# PCB-ETH-TALLY.net
KiCad netlist of a schematic drawn in EAGLE
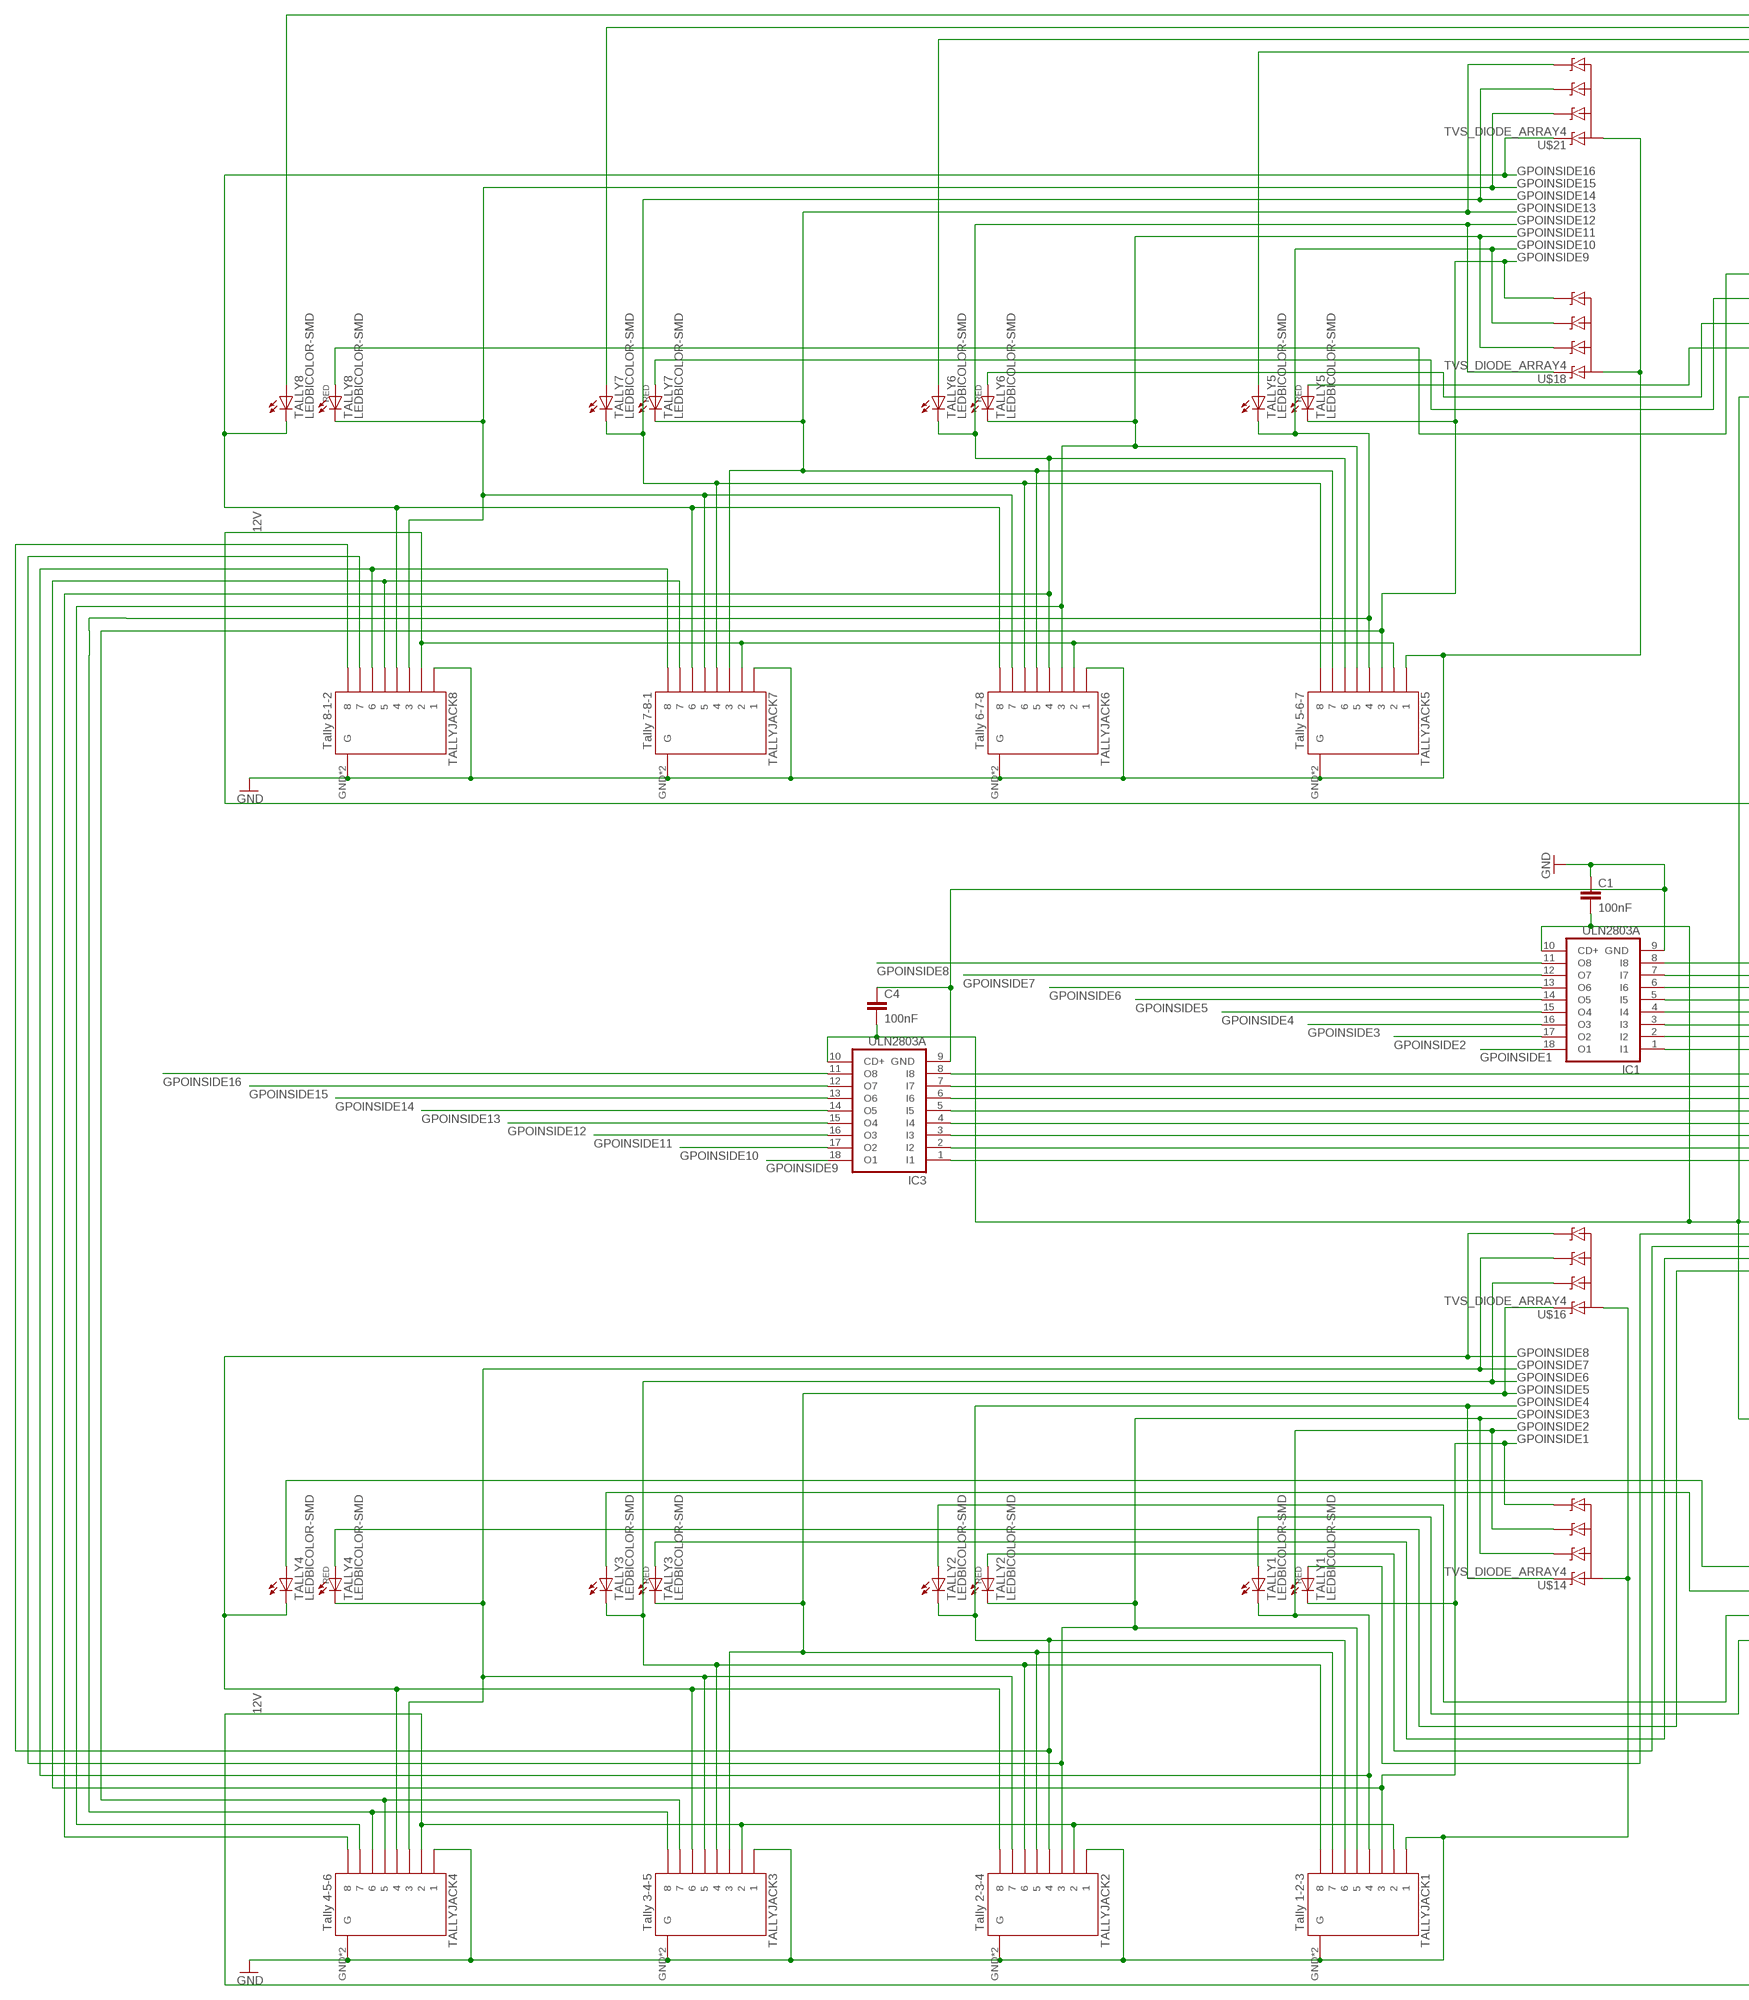
[diagram p0: schematic, sheet 1, part 1 of 2]
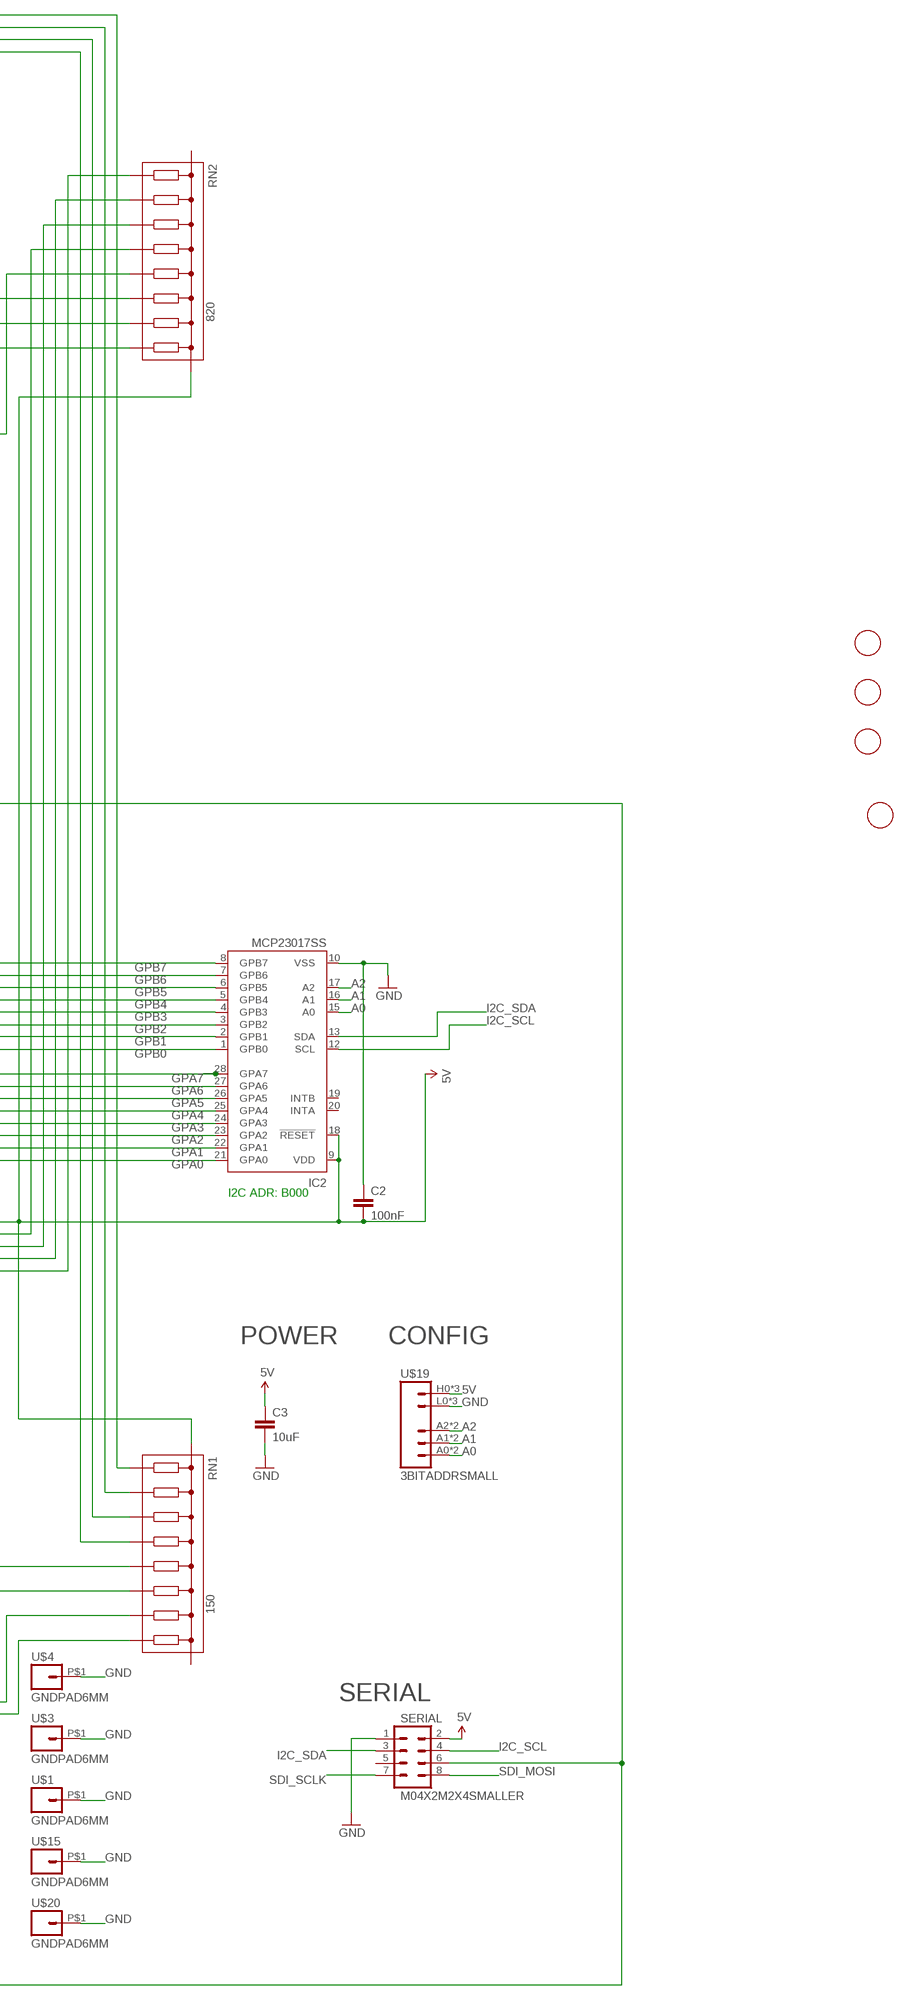
[diagram p1: schematic, sheet 1, part 2 of 2]

(export (version "E")
  (design (tool "Eeschema 10.0.6"))
  (components
    (comp (ref "C1")
      (value "100nF")
      (footprint "eagle-import:0805")
      (libsource (lib "eagle-import") (part "CAP0805"))
    )
    (comp (ref "C2")
      (value "100nF")
      (footprint "eagle-import:0603-CAP")
      (libsource (lib "eagle-import") (part "CAP0603-CAP"))
    )
    (comp (ref "C3")
      (value "10uF")
      (footprint "eagle-import:0805")
      (libsource (lib "eagle-import") (part "CAP0805"))
    )
    (comp (ref "C4")
      (value "100nF")
      (footprint "eagle-import:0805")
      (libsource (lib "eagle-import") (part "CAP0805"))
    )
    (comp (ref "IC1")
      (value "ULN2803A")
      (footprint "eagle-import:SO18W")
      (libsource (lib "eagle-import") (part "ULN2803ASO18W"))
    )
    (comp (ref "IC2")
      (value "MCP23017SS")
      (footprint "eagle-import:SSOP28")
      (fields (field (name "MF") "MICROCHIP") (field (name "MPN") "MCP23017-E/SS"))
      (libsource (lib "eagle-import") (part "MCP23017SS"))
    )
    (comp (ref "IC3")
      (value "ULN2803A")
      (footprint "eagle-import:SO18W")
      (libsource (lib "eagle-import") (part "ULN2803ASO18W"))
    )
    (comp (ref "RN1")
      (value "150")
      (footprint "eagle-import:EXBE")
      (libsource (lib "eagle-import") (part "EXBE"))
    )
    (comp (ref "RN2")
      (value "820")
      (footprint "eagle-import:EXBE")
      (libsource (lib "eagle-import") (part "EXBE"))
    )
    (comp (ref "SERIAL")
      (value "M04X2M2X4SMALLER")
      (footprint "eagle-import:M2X4SMALLER")
      (libsource (lib "eagle-import") (part "M04X2M2X4SMALLER"))
    )
    (comp (ref "TALLY1")
      (value "LEDBICOLOR-SMD")
      (footprint "eagle-import:LEDBICOLOR-SMD")
      (libsource (lib "eagle-import") (part "LEDBICOLOR-SMD"))
    )
    (comp (ref "TALLY2")
      (value "LEDBICOLOR-SMD")
      (footprint "eagle-import:LEDBICOLOR-SMD")
      (libsource (lib "eagle-import") (part "LEDBICOLOR-SMD"))
    )
    (comp (ref "TALLY3")
      (value "LEDBICOLOR-SMD")
      (footprint "eagle-import:LEDBICOLOR-SMD")
      (libsource (lib "eagle-import") (part "LEDBICOLOR-SMD"))
    )
    (comp (ref "TALLY4")
      (value "LEDBICOLOR-SMD")
      (footprint "eagle-import:LEDBICOLOR-SMD")
      (libsource (lib "eagle-import") (part "LEDBICOLOR-SMD"))
    )
    (comp (ref "TALLY5")
      (value "LEDBICOLOR-SMD")
      (footprint "eagle-import:LEDBICOLOR-SMD")
      (libsource (lib "eagle-import") (part "LEDBICOLOR-SMD"))
    )
    (comp (ref "TALLY6")
      (value "LEDBICOLOR-SMD")
      (footprint "eagle-import:LEDBICOLOR-SMD")
      (libsource (lib "eagle-import") (part "LEDBICOLOR-SMD"))
    )
    (comp (ref "TALLY7")
      (value "LEDBICOLOR-SMD")
      (footprint "eagle-import:LEDBICOLOR-SMD")
      (libsource (lib "eagle-import") (part "LEDBICOLOR-SMD"))
    )
    (comp (ref "TALLY8")
      (value "LEDBICOLOR-SMD")
      (footprint "eagle-import:LEDBICOLOR-SMD")
      (libsource (lib "eagle-import") (part "LEDBICOLOR-SMD"))
    )
    (comp (ref "TALLYJACK1")
      (value "Tally 1-2-3")
      (footprint "eagle-import:RJ45-8_GND_UPRIGHT")
      (libsource (lib "eagle-import") (part "RJ45-8_GNDUPRIGHT"))
    )
    (comp (ref "TALLYJACK2")
      (value "Tally 2-3-4")
      (footprint "eagle-import:RJ45-8_GND_UPRIGHT")
      (libsource (lib "eagle-import") (part "RJ45-8_GNDUPRIGHT"))
    )
    (comp (ref "TALLYJACK3")
      (value "Tally 3-4-5")
      (footprint "eagle-import:RJ45-8_GND_UPRIGHT")
      (libsource (lib "eagle-import") (part "RJ45-8_GNDUPRIGHT"))
    )
    (comp (ref "TALLYJACK4")
      (value "Tally 4-5-6")
      (footprint "eagle-import:RJ45-8_GND_UPRIGHT")
      (libsource (lib "eagle-import") (part "RJ45-8_GNDUPRIGHT"))
    )
    (comp (ref "TALLYJACK5")
      (value "Tally 5-6-7")
      (footprint "eagle-import:RJ45-8_GND_UPRIGHT")
      (libsource (lib "eagle-import") (part "RJ45-8_GNDUPRIGHT"))
    )
    (comp (ref "TALLYJACK6")
      (value "Tally 6-7-8")
      (footprint "eagle-import:RJ45-8_GND_UPRIGHT")
      (libsource (lib "eagle-import") (part "RJ45-8_GNDUPRIGHT"))
    )
    (comp (ref "TALLYJACK7")
      (value "Tally 7-8-1")
      (footprint "eagle-import:RJ45-8_GND_UPRIGHT")
      (libsource (lib "eagle-import") (part "RJ45-8_GNDUPRIGHT"))
    )
    (comp (ref "TALLYJACK8")
      (value "Tally 8-1-2")
      (footprint "eagle-import:RJ45-8_GND_UPRIGHT")
      (libsource (lib "eagle-import") (part "RJ45-8_GNDUPRIGHT"))
    )
    (comp (ref "U$1")
      (value "GNDPAD6MM")
      (footprint "eagle-import:3.2MMPAD6MM")
      (libsource (lib "eagle-import") (part "GNDPAD6MM"))
    )
    (comp (ref "U$3")
      (value "GNDPAD6MM")
      (footprint "eagle-import:3.2MMPAD6MM")
      (libsource (lib "eagle-import") (part "GNDPAD6MM"))
    )
    (comp (ref "U$4")
      (value "GNDPAD6MM")
      (footprint "eagle-import:3.2MMPAD6MM")
      (libsource (lib "eagle-import") (part "GNDPAD6MM"))
    )
    (comp (ref "U$5")
      (value "FIDUCIAL")
      (footprint "eagle-import:FIDUCIAL_1MM")
      (libsource (lib "eagle-import") (part "FIDUCIAL"))
    )
    (comp (ref "U$6")
      (value "FIDUCIAL")
      (footprint "eagle-import:FIDUCIAL_1MM")
      (libsource (lib "eagle-import") (part "FIDUCIAL"))
    )
    (comp (ref "U$8")
      (value "FIDUCIAL")
      (footprint "eagle-import:FIDUCIAL_1MM")
      (libsource (lib "eagle-import") (part "FIDUCIAL"))
    )
    (comp (ref "U$9")
      (value "FIDUCIAL")
      (footprint "eagle-import:FIDUCIAL_1MM")
      (libsource (lib "eagle-import") (part "FIDUCIAL"))
    )
    (comp (ref "U$14")
      (value "TVS_DIODE_ARRAY4")
      (footprint "eagle-import:SOT23-6L")
      (libsource (lib "eagle-import") (part "TVS_DIODE_ARRAY4"))
    )
    (comp (ref "U$15")
      (value "GNDPAD6MM")
      (footprint "eagle-import:3.2MMPAD6MM")
      (libsource (lib "eagle-import") (part "GNDPAD6MM"))
    )
    (comp (ref "U$16")
      (value "TVS_DIODE_ARRAY4")
      (footprint "eagle-import:SOT23-6L")
      (libsource (lib "eagle-import") (part "TVS_DIODE_ARRAY4"))
    )
    (comp (ref "U$18")
      (value "TVS_DIODE_ARRAY4")
      (footprint "eagle-import:SOT23-6L")
      (libsource (lib "eagle-import") (part "TVS_DIODE_ARRAY4"))
    )
    (comp (ref "U$19")
      (value "3BITADDRSMALL")
      (footprint "eagle-import:3BITADDR_SMALL")
      (libsource (lib "eagle-import") (part "3BITADDRSMALL"))
    )
    (comp (ref "U$20")
      (value "GNDPAD6MM")
      (footprint "eagle-import:3.2MMPAD6MM")
      (libsource (lib "eagle-import") (part "GNDPAD6MM"))
    )
    (comp (ref "U$21")
      (value "TVS_DIODE_ARRAY4")
      (footprint "eagle-import:SOT23-6L")
      (libsource (lib "eagle-import") (part "TVS_DIODE_ARRAY4"))
    )
  )
  (nets
    (net (code "1") (name "/12V") (class "Default")
      (node (ref "SERIAL") (pin "6") (pinfunction "6_6") (pintype "passive"))
      (node (ref "TALLYJACK1") (pin "2") (pinfunction "2_2") (pintype "bidirectional"))
      (node (ref "TALLYJACK2") (pin "2") (pinfunction "2_2") (pintype "bidirectional"))
      (node (ref "TALLYJACK3") (pin "2") (pinfunction "2_2") (pintype "bidirectional"))
      (node (ref "TALLYJACK4") (pin "2") (pinfunction "2_2") (pintype "bidirectional"))
      (node (ref "TALLYJACK5") (pin "2") (pinfunction "2_2") (pintype "bidirectional"))
      (node (ref "TALLYJACK6") (pin "2") (pinfunction "2_2") (pintype "bidirectional"))
      (node (ref "TALLYJACK7") (pin "2") (pinfunction "2_2") (pintype "bidirectional"))
      (node (ref "TALLYJACK8") (pin "2") (pinfunction "2_2") (pintype "bidirectional"))
    )
    (net (code "2") (name "/A0") (class "Default")
      (node (ref "IC2") (pin "15") (pinfunction "A0_15") (pintype "input"))
      (node (ref "U$19") (pin "A0") (pinfunction "A0_A0") (pintype "passive"))
      (node (ref "U$19") (pin "AS0") (pinfunction "A0_AS0") (pintype "passive"))
    )
    (net (code "3") (name "/A1") (class "Default")
      (node (ref "IC2") (pin "16") (pinfunction "A1_16") (pintype "input"))
      (node (ref "U$19") (pin "A1") (pinfunction "A1_A1") (pintype "passive"))
      (node (ref "U$19") (pin "AS1") (pinfunction "A1_AS1") (pintype "passive"))
    )
    (net (code "4") (name "/A2") (class "Default")
      (node (ref "IC2") (pin "17") (pinfunction "A2_17") (pintype "input"))
      (node (ref "U$19") (pin "A2") (pinfunction "A2_A2") (pintype "passive"))
      (node (ref "U$19") (pin "AS2") (pinfunction "A2_AS2") (pintype "passive"))
    )
    (net (code "5") (name "/GPA0") (class "Default")
      (node (ref "IC2") (pin "21") (pinfunction "GPA0_21") (pintype "bidirectional"))
      (node (ref "IC3") (pin "1") (pinfunction "I1_1") (pintype "input"))
    )
    (net (code "6") (name "/GPA1") (class "Default")
      (node (ref "IC2") (pin "22") (pinfunction "GPA1_22") (pintype "bidirectional"))
      (node (ref "IC3") (pin "2") (pinfunction "I2_2") (pintype "input"))
    )
    (net (code "7") (name "/GPA2") (class "Default")
      (node (ref "IC2") (pin "23") (pinfunction "GPA2_23") (pintype "bidirectional"))
      (node (ref "IC3") (pin "3") (pinfunction "I3_3") (pintype "input"))
    )
    (net (code "8") (name "/GPA3") (class "Default")
      (node (ref "IC2") (pin "24") (pinfunction "GPA3_24") (pintype "bidirectional"))
      (node (ref "IC3") (pin "4") (pinfunction "I4_4") (pintype "input"))
    )
    (net (code "9") (name "/GPA4") (class "Default")
      (node (ref "IC2") (pin "25") (pinfunction "GPA4_25") (pintype "bidirectional"))
      (node (ref "IC3") (pin "5") (pinfunction "I5_5") (pintype "input"))
    )
    (net (code "10") (name "/GPA5") (class "Default")
      (node (ref "IC2") (pin "26") (pinfunction "GPA5_26") (pintype "bidirectional"))
      (node (ref "IC3") (pin "6") (pinfunction "I6_6") (pintype "input"))
    )
    (net (code "11") (name "/GPA6") (class "Default")
      (node (ref "IC2") (pin "27") (pinfunction "GPA6_27") (pintype "bidirectional"))
      (node (ref "IC3") (pin "7") (pinfunction "I7_7") (pintype "input"))
    )
    (net (code "12") (name "/GPA7") (class "Default")
      (node (ref "IC2") (pin "28") (pinfunction "GPA7_28") (pintype "bidirectional"))
      (node (ref "IC3") (pin "8") (pinfunction "I8_8") (pintype "input"))
    )
    (net (code "13") (name "/GPB0") (class "Default")
      (node (ref "IC1") (pin "1") (pinfunction "I1_1") (pintype "input"))
      (node (ref "IC2") (pin "1") (pinfunction "GPB0_1") (pintype "bidirectional"))
    )
    (net (code "14") (name "/GPB1") (class "Default")
      (node (ref "IC1") (pin "2") (pinfunction "I2_2") (pintype "input"))
      (node (ref "IC2") (pin "2") (pinfunction "GPB1_2") (pintype "bidirectional"))
    )
    (net (code "15") (name "/GPB2") (class "Default")
      (node (ref "IC1") (pin "3") (pinfunction "I3_3") (pintype "input"))
      (node (ref "IC2") (pin "3") (pinfunction "GPB2_3") (pintype "bidirectional"))
    )
    (net (code "16") (name "/GPB3") (class "Default")
      (node (ref "IC1") (pin "4") (pinfunction "I4_4") (pintype "input"))
      (node (ref "IC2") (pin "4") (pinfunction "GPB3_4") (pintype "bidirectional"))
    )
    (net (code "17") (name "/GPB4") (class "Default")
      (node (ref "IC1") (pin "5") (pinfunction "I5_5") (pintype "input"))
      (node (ref "IC2") (pin "5") (pinfunction "GPB4_5") (pintype "bidirectional"))
    )
    (net (code "18") (name "/GPB5") (class "Default")
      (node (ref "IC1") (pin "6") (pinfunction "I6_6") (pintype "input"))
      (node (ref "IC2") (pin "6") (pinfunction "GPB5_6") (pintype "bidirectional"))
    )
    (net (code "19") (name "/GPB6") (class "Default")
      (node (ref "IC1") (pin "7") (pinfunction "I7_7") (pintype "input"))
      (node (ref "IC2") (pin "7") (pinfunction "GPB6_7") (pintype "bidirectional"))
    )
    (net (code "20") (name "/GPB7") (class "Default")
      (node (ref "IC1") (pin "8") (pinfunction "I8_8") (pintype "input"))
      (node (ref "IC2") (pin "8") (pinfunction "GPB7_8") (pintype "bidirectional"))
    )
    (net (code "21") (name "/GPOINSIDE1") (class "Default")
      (node (ref "IC1") (pin "18") (pinfunction "O1_18") (pintype "open_collector"))
      (node (ref "TALLY1") (pin "P$2") (pinfunction "C_P$2") (pintype "passive"))
      (node (ref "TALLYJACK1") (pin "3") (pinfunction "3_3") (pintype "bidirectional"))
      (node (ref "TALLYJACK7") (pin "7") (pinfunction "7_7") (pintype "bidirectional"))
      (node (ref "TALLYJACK8") (pin "5") (pinfunction "5_5") (pintype "bidirectional"))
      (node (ref "U$14") (pin "6") (pinfunction "D_6") (pintype "passive"))
    )
    (net (code "22") (name "/GPOINSIDE2") (class "Default")
      (node (ref "IC1") (pin "17") (pinfunction "O2_17") (pintype "open_collector"))
      (node (ref "TALLY1") (pin "P$4") (pinfunction "C1_P$4") (pintype "passive"))
      (node (ref "TALLYJACK1") (pin "4") (pinfunction "4_4") (pintype "bidirectional"))
      (node (ref "TALLYJACK7") (pin "8") (pinfunction "8_8") (pintype "bidirectional"))
      (node (ref "TALLYJACK8") (pin "6") (pinfunction "6_6") (pintype "bidirectional"))
      (node (ref "U$14") (pin "4") (pinfunction "C_4") (pintype "passive"))
    )
    (net (code "23") (name "/GPOINSIDE3") (class "Default")
      (node (ref "IC1") (pin "16") (pinfunction "O3_16") (pintype "open_collector"))
      (node (ref "TALLY2") (pin "P$2") (pinfunction "C_P$2") (pintype "passive"))
      (node (ref "TALLYJACK1") (pin "5") (pinfunction "5_5") (pintype "bidirectional"))
      (node (ref "TALLYJACK2") (pin "3") (pinfunction "3_3") (pintype "bidirectional"))
      (node (ref "TALLYJACK8") (pin "7") (pinfunction "7_7") (pintype "bidirectional"))
      (node (ref "U$14") (pin "3") (pinfunction "B_3") (pintype "passive"))
    )
    (net (code "24") (name "/GPOINSIDE4") (class "Default")
      (node (ref "IC1") (pin "15") (pinfunction "O4_15") (pintype "open_collector"))
      (node (ref "TALLY2") (pin "P$4") (pinfunction "C1_P$4") (pintype "passive"))
      (node (ref "TALLYJACK1") (pin "6") (pinfunction "6_6") (pintype "bidirectional"))
      (node (ref "TALLYJACK2") (pin "4") (pinfunction "4_4") (pintype "bidirectional"))
      (node (ref "TALLYJACK8") (pin "8") (pinfunction "8_8") (pintype "bidirectional"))
      (node (ref "U$14") (pin "1") (pinfunction "A_1") (pintype "passive"))
    )
    (net (code "25") (name "/GPOINSIDE5") (class "Default")
      (node (ref "IC1") (pin "14") (pinfunction "O5_14") (pintype "open_collector"))
      (node (ref "TALLY3") (pin "P$2") (pinfunction "C_P$2") (pintype "passive"))
      (node (ref "TALLYJACK1") (pin "7") (pinfunction "7_7") (pintype "bidirectional"))
      (node (ref "TALLYJACK2") (pin "5") (pinfunction "5_5") (pintype "bidirectional"))
      (node (ref "TALLYJACK3") (pin "3") (pinfunction "3_3") (pintype "bidirectional"))
      (node (ref "U$16") (pin "1") (pinfunction "A_1") (pintype "passive"))
    )
    (net (code "26") (name "/GPOINSIDE6") (class "Default")
      (node (ref "IC1") (pin "13") (pinfunction "O6_13") (pintype "open_collector"))
      (node (ref "TALLY3") (pin "P$4") (pinfunction "C1_P$4") (pintype "passive"))
      (node (ref "TALLYJACK1") (pin "8") (pinfunction "8_8") (pintype "bidirectional"))
      (node (ref "TALLYJACK2") (pin "6") (pinfunction "6_6") (pintype "bidirectional"))
      (node (ref "TALLYJACK3") (pin "4") (pinfunction "4_4") (pintype "bidirectional"))
      (node (ref "U$16") (pin "3") (pinfunction "B_3") (pintype "passive"))
    )
    (net (code "27") (name "/GPOINSIDE7") (class "Default")
      (node (ref "IC1") (pin "12") (pinfunction "O7_12") (pintype "open_collector"))
      (node (ref "TALLY4") (pin "P$2") (pinfunction "C_P$2") (pintype "passive"))
      (node (ref "TALLYJACK2") (pin "7") (pinfunction "7_7") (pintype "bidirectional"))
      (node (ref "TALLYJACK3") (pin "5") (pinfunction "5_5") (pintype "bidirectional"))
      (node (ref "TALLYJACK4") (pin "3") (pinfunction "3_3") (pintype "bidirectional"))
      (node (ref "U$16") (pin "4") (pinfunction "C_4") (pintype "passive"))
    )
    (net (code "28") (name "/GPOINSIDE8") (class "Default")
      (node (ref "IC1") (pin "11") (pinfunction "O8_11") (pintype "open_collector"))
      (node (ref "TALLY4") (pin "P$4") (pinfunction "C1_P$4") (pintype "passive"))
      (node (ref "TALLYJACK2") (pin "8") (pinfunction "8_8") (pintype "bidirectional"))
      (node (ref "TALLYJACK3") (pin "6") (pinfunction "6_6") (pintype "bidirectional"))
      (node (ref "TALLYJACK4") (pin "4") (pinfunction "4_4") (pintype "bidirectional"))
      (node (ref "U$16") (pin "6") (pinfunction "D_6") (pintype "passive"))
    )
    (net (code "29") (name "/GPOINSIDE9") (class "Default")
      (node (ref "IC3") (pin "18") (pinfunction "O1_18") (pintype "open_collector"))
      (node (ref "TALLY5") (pin "P$2") (pinfunction "C_P$2") (pintype "passive"))
      (node (ref "TALLYJACK3") (pin "7") (pinfunction "7_7") (pintype "bidirectional"))
      (node (ref "TALLYJACK4") (pin "5") (pinfunction "5_5") (pintype "bidirectional"))
      (node (ref "TALLYJACK5") (pin "3") (pinfunction "3_3") (pintype "bidirectional"))
      (node (ref "U$18") (pin "6") (pinfunction "D_6") (pintype "passive"))
    )
    (net (code "30") (name "/GPOINSIDE10") (class "Default")
      (node (ref "IC3") (pin "17") (pinfunction "O2_17") (pintype "open_collector"))
      (node (ref "TALLY5") (pin "P$4") (pinfunction "C1_P$4") (pintype "passive"))
      (node (ref "TALLYJACK3") (pin "8") (pinfunction "8_8") (pintype "bidirectional"))
      (node (ref "TALLYJACK4") (pin "6") (pinfunction "6_6") (pintype "bidirectional"))
      (node (ref "TALLYJACK5") (pin "4") (pinfunction "4_4") (pintype "bidirectional"))
      (node (ref "U$18") (pin "4") (pinfunction "C_4") (pintype "passive"))
    )
    (net (code "31") (name "/GPOINSIDE11") (class "Default")
      (node (ref "IC3") (pin "16") (pinfunction "O3_16") (pintype "open_collector"))
      (node (ref "TALLY6") (pin "P$2") (pinfunction "C_P$2") (pintype "passive"))
      (node (ref "TALLYJACK4") (pin "7") (pinfunction "7_7") (pintype "bidirectional"))
      (node (ref "TALLYJACK5") (pin "5") (pinfunction "5_5") (pintype "bidirectional"))
      (node (ref "TALLYJACK6") (pin "3") (pinfunction "3_3") (pintype "bidirectional"))
      (node (ref "U$18") (pin "3") (pinfunction "B_3") (pintype "passive"))
    )
    (net (code "32") (name "/GPOINSIDE12") (class "Default")
      (node (ref "IC3") (pin "15") (pinfunction "O4_15") (pintype "open_collector"))
      (node (ref "TALLY6") (pin "P$4") (pinfunction "C1_P$4") (pintype "passive"))
      (node (ref "TALLYJACK4") (pin "8") (pinfunction "8_8") (pintype "bidirectional"))
      (node (ref "TALLYJACK5") (pin "6") (pinfunction "6_6") (pintype "bidirectional"))
      (node (ref "TALLYJACK6") (pin "4") (pinfunction "4_4") (pintype "bidirectional"))
      (node (ref "U$18") (pin "1") (pinfunction "A_1") (pintype "passive"))
    )
    (net (code "33") (name "/GPOINSIDE13") (class "Default")
      (node (ref "IC3") (pin "14") (pinfunction "O5_14") (pintype "open_collector"))
      (node (ref "TALLY7") (pin "P$2") (pinfunction "C_P$2") (pintype "passive"))
      (node (ref "TALLYJACK5") (pin "7") (pinfunction "7_7") (pintype "bidirectional"))
      (node (ref "TALLYJACK6") (pin "5") (pinfunction "5_5") (pintype "bidirectional"))
      (node (ref "TALLYJACK7") (pin "3") (pinfunction "3_3") (pintype "bidirectional"))
      (node (ref "U$21") (pin "6") (pinfunction "D_6") (pintype "passive"))
    )
    (net (code "34") (name "/GPOINSIDE14") (class "Default")
      (node (ref "IC3") (pin "13") (pinfunction "O6_13") (pintype "open_collector"))
      (node (ref "TALLY7") (pin "P$4") (pinfunction "C1_P$4") (pintype "passive"))
      (node (ref "TALLYJACK5") (pin "8") (pinfunction "8_8") (pintype "bidirectional"))
      (node (ref "TALLYJACK6") (pin "6") (pinfunction "6_6") (pintype "bidirectional"))
      (node (ref "TALLYJACK7") (pin "4") (pinfunction "4_4") (pintype "bidirectional"))
      (node (ref "U$21") (pin "4") (pinfunction "C_4") (pintype "passive"))
    )
    (net (code "35") (name "/GPOINSIDE15") (class "Default")
      (node (ref "IC3") (pin "12") (pinfunction "O7_12") (pintype "open_collector"))
      (node (ref "TALLY8") (pin "P$2") (pinfunction "C_P$2") (pintype "passive"))
      (node (ref "TALLYJACK6") (pin "7") (pinfunction "7_7") (pintype "bidirectional"))
      (node (ref "TALLYJACK7") (pin "5") (pinfunction "5_5") (pintype "bidirectional"))
      (node (ref "TALLYJACK8") (pin "3") (pinfunction "3_3") (pintype "bidirectional"))
      (node (ref "U$21") (pin "3") (pinfunction "B_3") (pintype "passive"))
    )
    (net (code "36") (name "/GPOINSIDE16") (class "Default")
      (node (ref "IC3") (pin "11") (pinfunction "O8_11") (pintype "open_collector"))
      (node (ref "TALLY8") (pin "P$4") (pinfunction "C1_P$4") (pintype "passive"))
      (node (ref "TALLYJACK6") (pin "8") (pinfunction "8_8") (pintype "bidirectional"))
      (node (ref "TALLYJACK7") (pin "6") (pinfunction "6_6") (pintype "bidirectional"))
      (node (ref "TALLYJACK8") (pin "4") (pinfunction "4_4") (pintype "bidirectional"))
      (node (ref "U$21") (pin "1") (pinfunction "A_1") (pintype "passive"))
    )
    (net (code "37") (name "/I2C_SCL") (class "Default")
      (node (ref "IC2") (pin "12") (pinfunction "SCL_12") (pintype "input"))
      (node (ref "SERIAL") (pin "4") (pinfunction "4_4") (pintype "passive"))
    )
    (net (code "38") (name "/I2C_SDA") (class "Default")
      (node (ref "IC2") (pin "13") (pinfunction "SDA_13") (pintype "bidirectional"))
      (node (ref "SERIAL") (pin "3") (pinfunction "3_3") (pintype "passive"))
    )
    (net (code "39") (name "/SDI_MOSI") (class "Default")
      (node (ref "SERIAL") (pin "8") (pinfunction "8_8") (pintype "passive"))
    )
    (net (code "40") (name "/SDI_SCLK") (class "Default")
      (node (ref "SERIAL") (pin "7") (pinfunction "7_7") (pintype "passive"))
    )
    (net (code "41") (name "5V") (class "Default")
      (node (ref "C1") (pin "2") (pinfunction "2_2") (pintype "passive"))
      (node (ref "C2") (pin "2") (pinfunction "2_2") (pintype "passive"))
      (node (ref "C3") (pin "1") (pinfunction "1_1") (pintype "passive"))
      (node (ref "C4") (pin "2") (pinfunction "2_2") (pintype "passive"))
      (node (ref "IC1") (pin "10") (pinfunction "CD+_10") (pintype "passive"))
      (node (ref "IC2") (pin "18") (pinfunction "~{RESET}_18") (pintype "input"))
      (node (ref "IC2") (pin "9") (pinfunction "VDD_9") (pintype "power_in"))
      (node (ref "IC3") (pin "10") (pinfunction "CD+_10") (pintype "passive"))
      (node (ref "RN1") (pin "1") (pinfunction "POL_1") (pintype "passive"))
      (node (ref "RN2") (pin "6") (pinfunction "POL_6") (pintype "passive"))
      (node (ref "SERIAL") (pin "2") (pinfunction "2_2") (pintype "passive"))
      (node (ref "U$19") (pin "H0") (pinfunction "VCC_H0") (pintype "passive"))
      (node (ref "U$19") (pin "H1") (pinfunction "VCC_H1") (pintype "passive"))
      (node (ref "U$19") (pin "H2") (pinfunction "VCC_H2") (pintype "passive"))
    )
    (net (code "42") (name "GND") (class "Default")
      (node (ref "C1") (pin "1") (pinfunction "1_1") (pintype "passive"))
      (node (ref "C2") (pin "1") (pinfunction "1_1") (pintype "passive"))
      (node (ref "C3") (pin "2") (pinfunction "2_2") (pintype "passive"))
      (node (ref "C4") (pin "1") (pinfunction "1_1") (pintype "passive"))
      (node (ref "IC1") (pin "9") (pinfunction "GND_9") (pintype "power_in"))
      (node (ref "IC2") (pin "10") (pinfunction "VSS_10") (pintype "power_in"))
      (node (ref "IC3") (pin "9") (pinfunction "GND_9") (pintype "power_in"))
      (node (ref "SERIAL") (pin "1") (pinfunction "1_1") (pintype "passive"))
      (node (ref "TALLYJACK1") (pin "1") (pinfunction "1_1") (pintype "bidirectional"))
      (node (ref "TALLYJACK1") (pin "GND") (pinfunction "G_GND") (pintype "power_in"))
      (node (ref "TALLYJACK1") (pin "GND1") (pinfunction "G_GND1") (pintype "power_in"))
      (node (ref "TALLYJACK2") (pin "1") (pinfunction "1_1") (pintype "bidirectional"))
      (node (ref "TALLYJACK2") (pin "GND") (pinfunction "G_GND") (pintype "power_in"))
      (node (ref "TALLYJACK2") (pin "GND1") (pinfunction "G_GND1") (pintype "power_in"))
      (node (ref "TALLYJACK3") (pin "1") (pinfunction "1_1") (pintype "bidirectional"))
      (node (ref "TALLYJACK3") (pin "GND") (pinfunction "G_GND") (pintype "power_in"))
      (node (ref "TALLYJACK3") (pin "GND1") (pinfunction "G_GND1") (pintype "power_in"))
      (node (ref "TALLYJACK4") (pin "1") (pinfunction "1_1") (pintype "bidirectional"))
      (node (ref "TALLYJACK4") (pin "GND") (pinfunction "G_GND") (pintype "power_in"))
      (node (ref "TALLYJACK4") (pin "GND1") (pinfunction "G_GND1") (pintype "power_in"))
      (node (ref "TALLYJACK5") (pin "1") (pinfunction "1_1") (pintype "bidirectional"))
      (node (ref "TALLYJACK5") (pin "GND") (pinfunction "G_GND") (pintype "power_in"))
      (node (ref "TALLYJACK5") (pin "GND1") (pinfunction "G_GND1") (pintype "power_in"))
      (node (ref "TALLYJACK6") (pin "1") (pinfunction "1_1") (pintype "bidirectional"))
      (node (ref "TALLYJACK6") (pin "GND") (pinfunction "G_GND") (pintype "power_in"))
      (node (ref "TALLYJACK6") (pin "GND1") (pinfunction "G_GND1") (pintype "power_in"))
      (node (ref "TALLYJACK7") (pin "1") (pinfunction "1_1") (pintype "bidirectional"))
      (node (ref "TALLYJACK7") (pin "GND") (pinfunction "G_GND") (pintype "power_in"))
      (node (ref "TALLYJACK7") (pin "GND1") (pinfunction "G_GND1") (pintype "power_in"))
      (node (ref "TALLYJACK8") (pin "1") (pinfunction "1_1") (pintype "bidirectional"))
      (node (ref "TALLYJACK8") (pin "GND") (pinfunction "G_GND") (pintype "power_in"))
      (node (ref "TALLYJACK8") (pin "GND1") (pinfunction "G_GND1") (pintype "power_in"))
      (node (ref "U$1") (pin "P$1") (pinfunction "1_P$1") (pintype "passive"))
      (node (ref "U$14") (pin "2") (pinfunction "GND_2") (pintype "passive"))
      (node (ref "U$14") (pin "5") (pinfunction "GND_5") (pintype "passive"))
      (node (ref "U$15") (pin "P$1") (pinfunction "1_P$1") (pintype "passive"))
      (node (ref "U$16") (pin "2") (pinfunction "GND_2") (pintype "passive"))
      (node (ref "U$16") (pin "5") (pinfunction "GND_5") (pintype "passive"))
      (node (ref "U$18") (pin "2") (pinfunction "GND_2") (pintype "passive"))
      (node (ref "U$18") (pin "5") (pinfunction "GND_5") (pintype "passive"))
      (node (ref "U$19") (pin "L0") (pinfunction "GND_L0") (pintype "passive"))
      (node (ref "U$19") (pin "L1") (pinfunction "GND_L1") (pintype "passive"))
      (node (ref "U$19") (pin "L2") (pinfunction "GND_L2") (pintype "passive"))
      (node (ref "U$20") (pin "P$1") (pinfunction "1_P$1") (pintype "passive"))
      (node (ref "U$21") (pin "2") (pinfunction "GND_2") (pintype "passive"))
      (node (ref "U$21") (pin "5") (pinfunction "GND_5") (pintype "passive"))
      (node (ref "U$3") (pin "P$1") (pinfunction "1_P$1") (pintype "passive"))
      (node (ref "U$4") (pin "P$1") (pinfunction "1_P$1") (pintype "passive"))
    )
    (net (code "43") (name "Net-(RN1-1)") (class "Default")
      (node (ref "RN1") (pin "2") (pinfunction "1_2") (pintype "passive"))
      (node (ref "TALLY8") (pin "P$3") (pinfunction "A1_P$3") (pintype "passive"))
    )
    (net (code "44") (name "Net-(RN1-2)") (class "Default")
      (node (ref "RN1") (pin "3") (pinfunction "2_3") (pintype "passive"))
      (node (ref "TALLY7") (pin "P$3") (pinfunction "A1_P$3") (pintype "passive"))
    )
    (net (code "45") (name "Net-(RN1-3)") (class "Default")
      (node (ref "RN1") (pin "4") (pinfunction "3_4") (pintype "passive"))
      (node (ref "TALLY6") (pin "P$3") (pinfunction "A1_P$3") (pintype "passive"))
    )
    (net (code "46") (name "Net-(RN1-4)") (class "Default")
      (node (ref "RN1") (pin "5") (pinfunction "4_5") (pintype "passive"))
      (node (ref "TALLY5") (pin "P$3") (pinfunction "A1_P$3") (pintype "passive"))
    )
    (net (code "47") (name "Net-(RN1-5)") (class "Default")
      (node (ref "RN1") (pin "7") (pinfunction "5_7") (pintype "passive"))
      (node (ref "TALLY4") (pin "P$3") (pinfunction "A1_P$3") (pintype "passive"))
    )
    (net (code "48") (name "Net-(RN1-6)") (class "Default")
      (node (ref "RN1") (pin "8") (pinfunction "6_8") (pintype "passive"))
      (node (ref "TALLY3") (pin "P$3") (pinfunction "A1_P$3") (pintype "passive"))
    )
    (net (code "49") (name "Net-(RN1-7)") (class "Default")
      (node (ref "RN1") (pin "9") (pinfunction "7_9") (pintype "passive"))
      (node (ref "TALLY2") (pin "P$3") (pinfunction "A1_P$3") (pintype "passive"))
    )
    (net (code "50") (name "Net-(RN1-8)") (class "Default")
      (node (ref "RN1") (pin "10") (pinfunction "8_10") (pintype "passive"))
      (node (ref "TALLY1") (pin "P$3") (pinfunction "A1_P$3") (pintype "passive"))
    )
    (net (code "51") (name "Net-(RN2-1)") (class "Default")
      (node (ref "RN2") (pin "2") (pinfunction "1_2") (pintype "passive"))
      (node (ref "TALLY4") (pin "P$1") (pinfunction "A_P$1") (pintype "passive"))
    )
    (net (code "52") (name "Net-(RN2-2)") (class "Default")
      (node (ref "RN2") (pin "3") (pinfunction "2_3") (pintype "passive"))
      (node (ref "TALLY3") (pin "P$1") (pinfunction "A_P$1") (pintype "passive"))
    )
    (net (code "53") (name "Net-(RN2-3)") (class "Default")
      (node (ref "RN2") (pin "4") (pinfunction "3_4") (pintype "passive"))
      (node (ref "TALLY2") (pin "P$1") (pinfunction "A_P$1") (pintype "passive"))
    )
    (net (code "54") (name "Net-(RN2-4)") (class "Default")
      (node (ref "RN2") (pin "5") (pinfunction "4_5") (pintype "passive"))
      (node (ref "TALLY1") (pin "P$1") (pinfunction "A_P$1") (pintype "passive"))
    )
    (net (code "55") (name "Net-(RN2-5)") (class "Default")
      (node (ref "RN2") (pin "7") (pinfunction "5_7") (pintype "passive"))
      (node (ref "TALLY8") (pin "P$1") (pinfunction "A_P$1") (pintype "passive"))
    )
    (net (code "56") (name "Net-(RN2-6)") (class "Default")
      (node (ref "RN2") (pin "8") (pinfunction "6_8") (pintype "passive"))
      (node (ref "TALLY7") (pin "P$1") (pinfunction "A_P$1") (pintype "passive"))
    )
    (net (code "57") (name "Net-(RN2-7)") (class "Default")
      (node (ref "RN2") (pin "9") (pinfunction "7_9") (pintype "passive"))
      (node (ref "TALLY6") (pin "P$1") (pinfunction "A_P$1") (pintype "passive"))
    )
    (net (code "58") (name "Net-(RN2-8)") (class "Default")
      (node (ref "RN2") (pin "10") (pinfunction "8_10") (pintype "passive"))
      (node (ref "TALLY5") (pin "P$1") (pinfunction "A_P$1") (pintype "passive"))
    )
    (net (code "59") (name "unconnected-(IC2-INTA-Pad20)") (class "Default")
      (node (ref "IC2") (pin "20") (pinfunction "INTA_20") (pintype "output"))
    )
    (net (code "60") (name "unconnected-(IC2-INTB-Pad19)") (class "Default")
      (node (ref "IC2") (pin "19") (pinfunction "INTB_19") (pintype "output"))
    )
    (net (code "61") (name "unconnected-(RN1-POL-Pad6)") (class "Default")
      (node (ref "RN1") (pin "6") (pinfunction "POL_6") (pintype "passive"))
    )
    (net (code "62") (name "unconnected-(RN2-POL-Pad1)") (class "Default")
      (node (ref "RN2") (pin "1") (pinfunction "POL_1") (pintype "passive"))
    )
    (net (code "63") (name "unconnected-(SERIAL-Pad5)") (class "Default")
      (node (ref "SERIAL") (pin "5") (pinfunction "5_5") (pintype "passive"))
    )
  )
)
